# RPI_HAT_Flash_00.net
KiCad netlist of a schematic drawn in Altium Designer
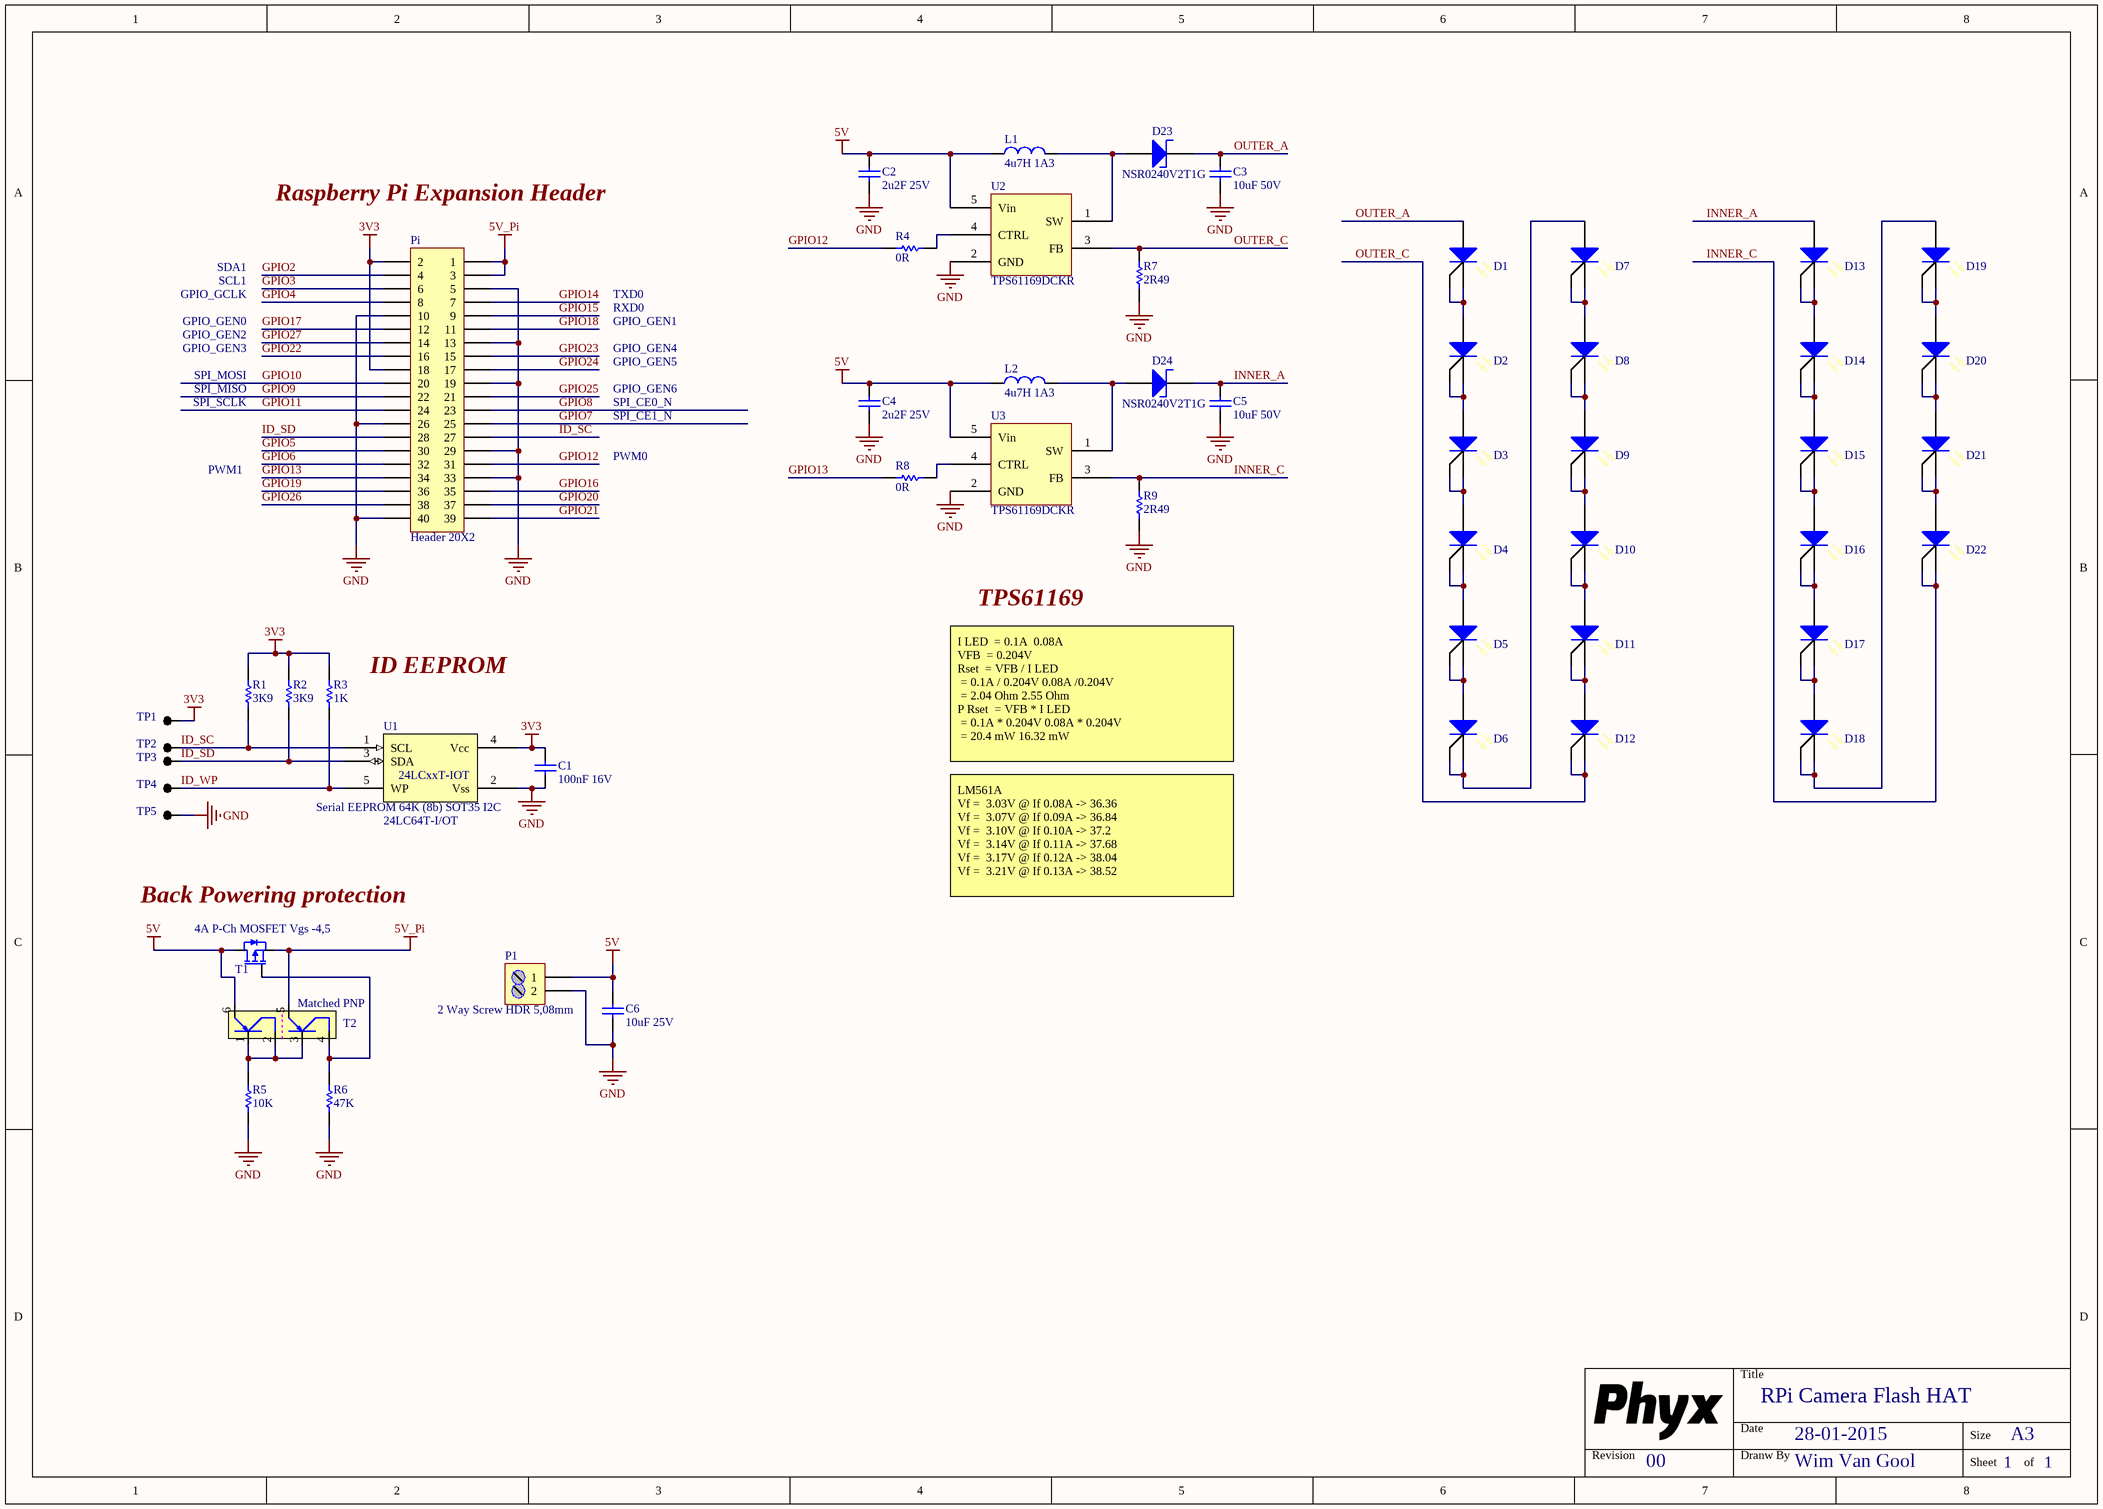
[diagram p0: RPI_HAT_Flash_00.SchDoc]

(export (version "E")
  (design (tool "Eeschema 10.0.6"))
  (components
    (comp (ref "C1")
      (value "100nF 16V")
      (footprint "C0603")
      (description "Capacitor Ceramic")
      (fields (field (name "Comment") "CAP_CERAMIC"))
      (libsource (lib "Phyx_Components") (part "CAP_CERAMIC"))
    )
    (comp (ref "C2")
      (value "2u2F 25V")
      (footprint "C0805")
      (description "Capacitor Ceramic")
      (fields (field (name "Comment") "CAP_CERAMIC"))
      (libsource (lib "Phyx_Components") (part "CAP_CERAMIC"))
    )
    (comp (ref "C3")
      (value "10uF 50V")
      (footprint "C1206")
      (description "Capacitor Ceramic")
      (fields (field (name "Comment") "CAP_CERAMIC"))
      (libsource (lib "Phyx_Components") (part "CAP_CERAMIC"))
    )
    (comp (ref "C4")
      (value "2u2F 25V")
      (footprint "C0805")
      (description "Capacitor Ceramic")
      (fields (field (name "Comment") "CAP_CERAMIC"))
      (libsource (lib "Phyx_Components") (part "CAP_CERAMIC"))
    )
    (comp (ref "C5")
      (value "10uF 50V")
      (footprint "C1206")
      (description "Capacitor Ceramic")
      (fields (field (name "Comment") "CAP_CERAMIC"))
      (libsource (lib "Phyx_Components") (part "CAP_CERAMIC"))
    )
    (comp (ref "C6")
      (value "10uF 25V")
      (footprint "C1206")
      (description "Capacitor Ceramic")
      (fields (field (name "Comment") "CAP_CERAMIC"))
      (libsource (lib "Phyx_Components") (part "CAP_CERAMIC"))
    )
    (comp (ref "D1")
      (value "5630 LM561A Samsung LED")
      (footprint "LED_LM561A")
      (description "=Description")
      (libsource (lib "Phyx_Components") (part "LED_LM561A"))
    )
    (comp (ref "D2")
      (value "5630 LM561A Samsung LED")
      (footprint "LED_LM561A")
      (description "=Description")
      (libsource (lib "Phyx_Components") (part "LED_LM561A"))
    )
    (comp (ref "D3")
      (value "5630 LM561A Samsung LED")
      (footprint "LED_LM561A")
      (description "=Description")
      (libsource (lib "Phyx_Components") (part "LED_LM561A"))
    )
    (comp (ref "D4")
      (value "5630 LM561A Samsung LED")
      (footprint "LED_LM561A")
      (description "=Description")
      (libsource (lib "Phyx_Components") (part "LED_LM561A"))
    )
    (comp (ref "D5")
      (value "5630 LM561A Samsung LED")
      (footprint "LED_LM561A")
      (description "=Description")
      (libsource (lib "Phyx_Components") (part "LED_LM561A"))
    )
    (comp (ref "D6")
      (value "5630 LM561A Samsung LED")
      (footprint "LED_LM561A")
      (description "=Description")
      (libsource (lib "Phyx_Components") (part "LED_LM561A"))
    )
    (comp (ref "D7")
      (value "5630 LM561A Samsung LED")
      (footprint "LED_LM561A")
      (description "=Description")
      (libsource (lib "Phyx_Components") (part "LED_LM561A"))
    )
    (comp (ref "D8")
      (value "5630 LM561A Samsung LED")
      (footprint "LED_LM561A")
      (description "=Description")
      (libsource (lib "Phyx_Components") (part "LED_LM561A"))
    )
    (comp (ref "D9")
      (value "5630 LM561A Samsung LED")
      (footprint "LED_LM561A")
      (description "=Description")
      (libsource (lib "Phyx_Components") (part "LED_LM561A"))
    )
    (comp (ref "D10")
      (value "5630 LM561A Samsung LED")
      (footprint "LED_LM561A")
      (description "=Description")
      (libsource (lib "Phyx_Components") (part "LED_LM561A"))
    )
    (comp (ref "D11")
      (value "5630 LM561A Samsung LED")
      (footprint "LED_LM561A")
      (description "=Description")
      (libsource (lib "Phyx_Components") (part "LED_LM561A"))
    )
    (comp (ref "D12")
      (value "5630 LM561A Samsung LED")
      (footprint "LED_LM561A")
      (description "=Description")
      (libsource (lib "Phyx_Components") (part "LED_LM561A"))
    )
    (comp (ref "D13")
      (value "5630 LM561A Samsung LED")
      (footprint "LED_LM561A")
      (description "=Description")
      (libsource (lib "Phyx_Components") (part "LED_LM561A"))
    )
    (comp (ref "D14")
      (value "5630 LM561A Samsung LED")
      (footprint "LED_LM561A")
      (description "=Description")
      (libsource (lib "Phyx_Components") (part "LED_LM561A"))
    )
    (comp (ref "D15")
      (value "5630 LM561A Samsung LED")
      (footprint "LED_LM561A")
      (description "=Description")
      (libsource (lib "Phyx_Components") (part "LED_LM561A"))
    )
    (comp (ref "D16")
      (value "5630 LM561A Samsung LED")
      (footprint "LED_LM561A")
      (description "=Description")
      (libsource (lib "Phyx_Components") (part "LED_LM561A"))
    )
    (comp (ref "D17")
      (value "5630 LM561A Samsung LED")
      (footprint "LED_LM561A")
      (description "=Description")
      (libsource (lib "Phyx_Components") (part "LED_LM561A"))
    )
    (comp (ref "D18")
      (value "5630 LM561A Samsung LED")
      (footprint "LED_LM561A")
      (description "=Description")
      (libsource (lib "Phyx_Components") (part "LED_LM561A"))
    )
    (comp (ref "D19")
      (value "5630 LM561A Samsung LED")
      (footprint "LED_LM561A")
      (description "=Description")
      (libsource (lib "Phyx_Components") (part "LED_LM561A"))
    )
    (comp (ref "D20")
      (value "5630 LM561A Samsung LED")
      (footprint "LED_LM561A")
      (description "=Description")
      (libsource (lib "Phyx_Components") (part "LED_LM561A"))
    )
    (comp (ref "D21")
      (value "5630 LM561A Samsung LED")
      (footprint "LED_LM561A")
      (description "=Description")
      (libsource (lib "Phyx_Components") (part "LED_LM561A"))
    )
    (comp (ref "D22")
      (value "5630 LM561A Samsung LED")
      (footprint "LED_LM561A")
      (description "=Description")
      (libsource (lib "Phyx_Components") (part "LED_LM561A"))
    )
    (comp (ref "D23")
      (value "NSR0240V2T1G")
      (footprint "ON_SOD-523")
      (description "=Description")
      (fields (field (name "Comment") "NSR0240V2T1G Schottky ULTRAFAST, 200MA, 40V"))
      (libsource (lib "Phyx_Components") (part "Schottky_CA"))
    )
    (comp (ref "D24")
      (value "NSR0240V2T1G")
      (footprint "ON_SOD-523")
      (description "=Description")
      (fields (field (name "Comment") "NSR0240V2T1G Schottky ULTRAFAST, 200MA, 40V"))
      (libsource (lib "Phyx_Components") (part "Schottky_CA"))
    )
    (comp (ref "L1")
      (value "4u7H 1A3")
      (footprint "LPS4018")
      (fields (field (name "Comment") "LPS4018-472MRB"))
      (libsource (lib "Phyx_Components") (part "INDUCTOR"))
    )
    (comp (ref "L2")
      (value "4u7H 1A3")
      (footprint "LPS4018")
      (fields (field (name "Comment") "LPS4018-472MRB"))
      (libsource (lib "Phyx_Components") (part "INDUCTOR"))
    )
    (comp (ref "P1")
      (value "2 Way Screw HDR 5,08mm")
      (footprint "TERM_BLK-0508-2-90")
      (libsource (lib "Phyx_Components") (part "TERM_BLCK_2"))
    )
    (comp (ref "Pi")
      (value "Header 20X2")
      (footprint "RCPT2X20")
      (description "=Description")
      (libsource (lib "Phyx_Components") (part "Header 20X2"))
    )
    (comp (ref "R1")
      (value "3K9")
      (footprint "R0603")
      (fields (field (name "Comment") "RESISTOR"))
      (libsource (lib "Phyx_Components") (part "RESISTOR"))
    )
    (comp (ref "R2")
      (value "3K9")
      (footprint "R0603")
      (fields (field (name "Comment") "RESISTOR"))
      (libsource (lib "Phyx_Components") (part "RESISTOR"))
    )
    (comp (ref "R3")
      (value "1K")
      (footprint "R0603")
      (fields (field (name "Comment") "RESISTOR"))
      (libsource (lib "Phyx_Components") (part "RESISTOR"))
    )
    (comp (ref "R4")
      (value "0R")
      (footprint "R0603")
      (fields (field (name "Comment") "RESISTOR"))
      (libsource (lib "Phyx_Components") (part "RESISTOR"))
    )
    (comp (ref "R5")
      (value "10K")
      (footprint "R0603")
      (fields (field (name "Comment") "RESISTOR"))
      (libsource (lib "Phyx_Components") (part "RESISTOR"))
    )
    (comp (ref "R6")
      (value "47K")
      (footprint "R0603")
      (fields (field (name "Comment") "RESISTOR"))
      (libsource (lib "Phyx_Components") (part "RESISTOR"))
    )
    (comp (ref "R7")
      (value "2R49")
      (footprint "R0603")
      (fields (field (name "Comment") "RESISTOR"))
      (libsource (lib "Phyx_Components") (part "RESISTOR"))
    )
    (comp (ref "R8")
      (value "0R")
      (footprint "R0603")
      (fields (field (name "Comment") "RESISTOR"))
      (libsource (lib "Phyx_Components") (part "RESISTOR"))
    )
    (comp (ref "R9")
      (value "2R49")
      (footprint "R0603")
      (fields (field (name "Comment") "RESISTOR"))
      (libsource (lib "Phyx_Components") (part "RESISTOR"))
    )
    (comp (ref "T1")
      (value "4A P-Ch MOSFET Vgs -4,5")
      (footprint "SOT23-3")
      (description "=Description")
      (libsource (lib "Phyx_Components") (part "P_MOSFET_GSD"))
    )
    (comp (ref "T2")
      (value "Matched PNP")
      (footprint "SOT23-6")
      (libsource (lib "Phyx_Components") (part "DMMT5401"))
    )
    (comp (ref "TP1")
      (value "TEST_PAD")
      (footprint "TP_1.2mm_0.6mm")
      (libsource (lib "Phyx_Components") (part "TEST_PAD"))
    )
    (comp (ref "TP2")
      (value "TEST_PAD")
      (footprint "TP_1.2mm_0.6mm")
      (libsource (lib "Phyx_Components") (part "TEST_PAD"))
    )
    (comp (ref "TP3")
      (value "TEST_PAD")
      (footprint "TP_1.2mm_0.6mm")
      (libsource (lib "Phyx_Components") (part "TEST_PAD"))
    )
    (comp (ref "TP4")
      (value "TEST_PAD")
      (footprint "TP_1.2mm_0.6mm")
      (libsource (lib "Phyx_Components") (part "TEST_PAD"))
    )
    (comp (ref "TP5")
      (value "TEST_PAD")
      (footprint "TP_1.2mm_0.6mm")
      (libsource (lib "Phyx_Components") (part "TEST_PAD"))
    )
    (comp (ref "U1")
      (value "Serial EEPROM 64K (8b) SOT35 I2C")
      (footprint "SOT23-5")
      (description "=Description")
      (fields (field (name "ALTIUM_VALUE") "24LC64T-I/OT"))
      (libsource (lib "Phyx_Components") (part "24LCxxT-IOT"))
    )
    (comp (ref "U2")
      (value "TPS61169DCKR")
      (footprint "TI-DCK-R-PDSO-G5")
      (description "=Description")
      (fields (field (name "Comment") "TPS61169 38-V Boost WLED Driver with PWM"))
      (libsource (lib "Phyx_Components") (part "TPS61169"))
    )
    (comp (ref "U3")
      (value "TPS61169DCKR")
      (footprint "TI-DCK-R-PDSO-G5")
      (description "=Description")
      (fields (field (name "Comment") "TPS61169 38-V Boost WLED Driver with PWM"))
      (libsource (lib "Phyx_Components") (part "TPS61169"))
    )
  )
  (nets
    (net (code "1") (name "/GPIO2") (class "Default")
      (node (ref "Pi") (pin "4") (pinfunction "4_4") (pintype "passive"))
    )
    (net (code "2") (name "/GPIO3") (class "Default")
      (node (ref "Pi") (pin "6") (pinfunction "6_6") (pintype "passive"))
    )
    (net (code "3") (name "/GPIO4") (class "Default")
      (node (ref "Pi") (pin "8") (pinfunction "8_8") (pintype "passive"))
    )
    (net (code "4") (name "/GPIO5") (class "Default")
      (node (ref "Pi") (pin "30") (pinfunction "30_30") (pintype "passive"))
    )
    (net (code "5") (name "/GPIO6") (class "Default")
      (node (ref "Pi") (pin "32") (pinfunction "32_32") (pintype "passive"))
    )
    (net (code "6") (name "/GPIO7") (class "Default")
      (node (ref "Pi") (pin "25") (pinfunction "25_25") (pintype "passive"))
    )
    (net (code "7") (name "/GPIO8") (class "Default")
      (node (ref "Pi") (pin "23") (pinfunction "23_23") (pintype "passive"))
    )
    (net (code "8") (name "/GPIO9") (class "Default")
      (node (ref "Pi") (pin "22") (pinfunction "22_22") (pintype "passive"))
    )
    (net (code "9") (name "/GPIO10") (class "Default")
      (node (ref "Pi") (pin "20") (pinfunction "20_20") (pintype "passive"))
    )
    (net (code "10") (name "/GPIO11") (class "Default")
      (node (ref "Pi") (pin "24") (pinfunction "24_24") (pintype "passive"))
    )
    (net (code "11") (name "/GPIO12") (class "Default")
      (node (ref "Pi") (pin "31") (pinfunction "31_31") (pintype "passive"))
      (node (ref "R4") (pin "2") (pinfunction "2_2") (pintype "passive"))
    )
    (net (code "12") (name "/GPIO13") (class "Default")
      (node (ref "Pi") (pin "34") (pinfunction "34_34") (pintype "passive"))
      (node (ref "R8") (pin "2") (pinfunction "2_2") (pintype "passive"))
    )
    (net (code "13") (name "/GPIO14") (class "Default")
      (node (ref "Pi") (pin "7") (pinfunction "7_7") (pintype "passive"))
    )
    (net (code "14") (name "/GPIO15") (class "Default")
      (node (ref "Pi") (pin "9") (pinfunction "9_9") (pintype "passive"))
    )
    (net (code "15") (name "/GPIO16") (class "Default")
      (node (ref "Pi") (pin "35") (pinfunction "35_35") (pintype "passive"))
    )
    (net (code "16") (name "/GPIO17") (class "Default")
      (node (ref "Pi") (pin "12") (pinfunction "12_12") (pintype "passive"))
    )
    (net (code "17") (name "/GPIO18") (class "Default")
      (node (ref "Pi") (pin "11") (pinfunction "11_11") (pintype "passive"))
    )
    (net (code "18") (name "/GPIO19") (class "Default")
      (node (ref "Pi") (pin "36") (pinfunction "36_36") (pintype "passive"))
    )
    (net (code "19") (name "/GPIO20") (class "Default")
      (node (ref "Pi") (pin "37") (pinfunction "37_37") (pintype "passive"))
    )
    (net (code "20") (name "/GPIO21") (class "Default")
      (node (ref "Pi") (pin "39") (pinfunction "39_39") (pintype "passive"))
    )
    (net (code "21") (name "/GPIO22") (class "Default")
      (node (ref "Pi") (pin "16") (pinfunction "16_16") (pintype "passive"))
    )
    (net (code "22") (name "/GPIO23") (class "Default")
      (node (ref "Pi") (pin "15") (pinfunction "15_15") (pintype "passive"))
    )
    (net (code "23") (name "/GPIO24") (class "Default")
      (node (ref "Pi") (pin "17") (pinfunction "17_17") (pintype "passive"))
    )
    (net (code "24") (name "/GPIO25") (class "Default")
      (node (ref "Pi") (pin "21") (pinfunction "21_21") (pintype "passive"))
    )
    (net (code "25") (name "/GPIO26") (class "Default")
      (node (ref "Pi") (pin "38") (pinfunction "38_38") (pintype "passive"))
    )
    (net (code "26") (name "/GPIO27") (class "Default")
      (node (ref "Pi") (pin "14") (pinfunction "14_14") (pintype "passive"))
    )
    (net (code "27") (name "/ID_SC") (class "Default")
      (node (ref "Pi") (pin "27") (pinfunction "27_27") (pintype "passive"))
      (node (ref "R1") (pin "2") (pinfunction "2_2") (pintype "passive"))
      (node (ref "TP2") (pin "1") (pinfunction "1_1") (pintype "passive"))
      (node (ref "U1") (pin "1") (pinfunction "SCL_1") (pintype "input"))
    )
    (net (code "28") (name "/ID_SD") (class "Default")
      (node (ref "Pi") (pin "28") (pinfunction "28_28") (pintype "passive"))
      (node (ref "R2") (pin "2") (pinfunction "2_2") (pintype "passive"))
      (node (ref "TP3") (pin "1") (pinfunction "1_1") (pintype "passive"))
      (node (ref "U1") (pin "3") (pinfunction "SDA_3") (pintype "bidirectional"))
    )
    (net (code "29") (name "/ID_WP") (class "Default")
      (node (ref "R3") (pin "2") (pinfunction "2_2") (pintype "passive"))
      (node (ref "TP4") (pin "1") (pinfunction "1_1") (pintype "passive"))
      (node (ref "U1") (pin "5") (pinfunction "WP_5") (pintype "passive"))
    )
    (net (code "30") (name "/INNER_A") (class "Default")
      (node (ref "C5") (pin "1") (pinfunction "1_1") (pintype "passive"))
      (node (ref "D13") (pin "1") (pinfunction "A_1") (pintype "passive"))
      (node (ref "D24") (pin "1") (pinfunction "C_1") (pintype "passive"))
    )
    (net (code "31") (name "/INNER_C") (class "Default")
      (node (ref "D22") (pin "2") (pinfunction "K_2") (pintype "passive"))
      (node (ref "D22") (pin "3") (pinfunction "K_3") (pintype "passive"))
      (node (ref "R9") (pin "1") (pinfunction "1_1") (pintype "passive"))
      (node (ref "U3") (pin "3") (pinfunction "FB_3") (pintype "passive"))
    )
    (net (code "32") (name "/OUTER_A") (class "Default")
      (node (ref "C3") (pin "1") (pinfunction "1_1") (pintype "passive"))
      (node (ref "D1") (pin "1") (pinfunction "A_1") (pintype "passive"))
      (node (ref "D23") (pin "1") (pinfunction "C_1") (pintype "passive"))
    )
    (net (code "33") (name "/OUTER_C") (class "Default")
      (node (ref "D12") (pin "2") (pinfunction "K_2") (pintype "passive"))
      (node (ref "D12") (pin "3") (pinfunction "K_3") (pintype "passive"))
      (node (ref "R7") (pin "1") (pinfunction "1_1") (pintype "passive"))
      (node (ref "U2") (pin "3") (pinfunction "FB_3") (pintype "passive"))
    )
    (net (code "34") (name "3V3") (class "Default")
      (node (ref "C1") (pin "1") (pinfunction "1_1") (pintype "passive"))
      (node (ref "Pi") (pin "18") (pinfunction "18_18") (pintype "passive"))
      (node (ref "Pi") (pin "2") (pinfunction "2_2") (pintype "passive"))
      (node (ref "R1") (pin "1") (pinfunction "1_1") (pintype "passive"))
      (node (ref "R2") (pin "1") (pinfunction "1_1") (pintype "passive"))
      (node (ref "R3") (pin "1") (pinfunction "1_1") (pintype "passive"))
      (node (ref "TP1") (pin "1") (pinfunction "1_1") (pintype "passive"))
      (node (ref "U1") (pin "4") (pinfunction "Vcc_4") (pintype "passive"))
    )
    (net (code "35") (name "5V") (class "Default")
      (node (ref "C2") (pin "1") (pinfunction "1_1") (pintype "passive"))
      (node (ref "C4") (pin "1") (pinfunction "1_1") (pintype "passive"))
      (node (ref "C6") (pin "1") (pinfunction "1_1") (pintype "passive"))
      (node (ref "L1") (pin "1") (pinfunction "1_1") (pintype "passive"))
      (node (ref "L2") (pin "1") (pinfunction "1_1") (pintype "passive"))
      (node (ref "P1") (pin "1") (pinfunction "1_1") (pintype "passive"))
      (node (ref "T1") (pin "3") (pinfunction "D_3") (pintype "passive"))
      (node (ref "T2") (pin "6") (pinfunction "E_6") (pintype "passive"))
      (node (ref "U2") (pin "5") (pinfunction "Vin_5") (pintype "passive"))
      (node (ref "U3") (pin "5") (pinfunction "Vin_5") (pintype "passive"))
    )
    (net (code "36") (name "5V_Pi") (class "Default")
      (node (ref "Pi") (pin "1") (pinfunction "1_1") (pintype "passive"))
      (node (ref "Pi") (pin "3") (pinfunction "3_3") (pintype "passive"))
      (node (ref "T1") (pin "2") (pinfunction "S_2") (pintype "passive"))
      (node (ref "T2") (pin "5") (pinfunction "E_5") (pintype "passive"))
    )
    (net (code "37") (name "GND") (class "Default")
      (node (ref "C1") (pin "2") (pinfunction "2_2") (pintype "passive"))
      (node (ref "C2") (pin "2") (pinfunction "2_2") (pintype "passive"))
      (node (ref "C3") (pin "2") (pinfunction "2_2") (pintype "passive"))
      (node (ref "C4") (pin "2") (pinfunction "2_2") (pintype "passive"))
      (node (ref "C5") (pin "2") (pinfunction "2_2") (pintype "passive"))
      (node (ref "C6") (pin "2") (pinfunction "2_2") (pintype "passive"))
      (node (ref "P1") (pin "2") (pinfunction "2_2") (pintype "passive"))
      (node (ref "Pi") (pin "10") (pinfunction "10_10") (pintype "passive"))
      (node (ref "Pi") (pin "13") (pinfunction "13_13") (pintype "passive"))
      (node (ref "Pi") (pin "19") (pinfunction "19_19") (pintype "passive"))
      (node (ref "Pi") (pin "26") (pinfunction "26_26") (pintype "passive"))
      (node (ref "Pi") (pin "29") (pinfunction "29_29") (pintype "passive"))
      (node (ref "Pi") (pin "33") (pinfunction "33_33") (pintype "passive"))
      (node (ref "Pi") (pin "40") (pinfunction "40_40") (pintype "passive"))
      (node (ref "Pi") (pin "5") (pinfunction "5_5") (pintype "passive"))
      (node (ref "R5") (pin "2") (pinfunction "2_2") (pintype "passive"))
      (node (ref "R6") (pin "2") (pinfunction "2_2") (pintype "passive"))
      (node (ref "R7") (pin "2") (pinfunction "2_2") (pintype "passive"))
      (node (ref "R9") (pin "2") (pinfunction "2_2") (pintype "passive"))
      (node (ref "TP5") (pin "1") (pinfunction "1_1") (pintype "passive"))
      (node (ref "U1") (pin "2") (pinfunction "Vss_2") (pintype "passive"))
      (node (ref "U2") (pin "2") (pinfunction "GND_2") (pintype "passive"))
      (node (ref "U3") (pin "2") (pinfunction "GND_2") (pintype "passive"))
    )
    (net (code "38") (name "Net-(D2-A)") (class "Default")
      (node (ref "D1") (pin "2") (pinfunction "K_2") (pintype "passive"))
      (node (ref "D1") (pin "3") (pinfunction "K_3") (pintype "passive"))
      (node (ref "D2") (pin "1") (pinfunction "A_1") (pintype "passive"))
    )
    (net (code "39") (name "Net-(D3-A)") (class "Default")
      (node (ref "D2") (pin "2") (pinfunction "K_2") (pintype "passive"))
      (node (ref "D2") (pin "3") (pinfunction "K_3") (pintype "passive"))
      (node (ref "D3") (pin "1") (pinfunction "A_1") (pintype "passive"))
    )
    (net (code "40") (name "Net-(D4-A)") (class "Default")
      (node (ref "D3") (pin "2") (pinfunction "K_2") (pintype "passive"))
      (node (ref "D3") (pin "3") (pinfunction "K_3") (pintype "passive"))
      (node (ref "D4") (pin "1") (pinfunction "A_1") (pintype "passive"))
    )
    (net (code "41") (name "Net-(D5-A)") (class "Default")
      (node (ref "D4") (pin "2") (pinfunction "K_2") (pintype "passive"))
      (node (ref "D4") (pin "3") (pinfunction "K_3") (pintype "passive"))
      (node (ref "D5") (pin "1") (pinfunction "A_1") (pintype "passive"))
    )
    (net (code "42") (name "Net-(D6-A)") (class "Default")
      (node (ref "D5") (pin "2") (pinfunction "K_2") (pintype "passive"))
      (node (ref "D5") (pin "3") (pinfunction "K_3") (pintype "passive"))
      (node (ref "D6") (pin "1") (pinfunction "A_1") (pintype "passive"))
    )
    (net (code "43") (name "Net-(D7-A)") (class "Default")
      (node (ref "D6") (pin "2") (pinfunction "K_2") (pintype "passive"))
      (node (ref "D6") (pin "3") (pinfunction "K_3") (pintype "passive"))
      (node (ref "D7") (pin "1") (pinfunction "A_1") (pintype "passive"))
    )
    (net (code "44") (name "Net-(D8-A)") (class "Default")
      (node (ref "D7") (pin "2") (pinfunction "K_2") (pintype "passive"))
      (node (ref "D7") (pin "3") (pinfunction "K_3") (pintype "passive"))
      (node (ref "D8") (pin "1") (pinfunction "A_1") (pintype "passive"))
    )
    (net (code "45") (name "Net-(D9-A)") (class "Default")
      (node (ref "D8") (pin "2") (pinfunction "K_2") (pintype "passive"))
      (node (ref "D8") (pin "3") (pinfunction "K_3") (pintype "passive"))
      (node (ref "D9") (pin "1") (pinfunction "A_1") (pintype "passive"))
    )
    (net (code "46") (name "Net-(D10-A)") (class "Default")
      (node (ref "D10") (pin "1") (pinfunction "A_1") (pintype "passive"))
      (node (ref "D9") (pin "2") (pinfunction "K_2") (pintype "passive"))
      (node (ref "D9") (pin "3") (pinfunction "K_3") (pintype "passive"))
    )
    (net (code "47") (name "Net-(D11-A)") (class "Default")
      (node (ref "D10") (pin "2") (pinfunction "K_2") (pintype "passive"))
      (node (ref "D10") (pin "3") (pinfunction "K_3") (pintype "passive"))
      (node (ref "D11") (pin "1") (pinfunction "A_1") (pintype "passive"))
    )
    (net (code "48") (name "Net-(D12-A)") (class "Default")
      (node (ref "D11") (pin "2") (pinfunction "K_2") (pintype "passive"))
      (node (ref "D11") (pin "3") (pinfunction "K_3") (pintype "passive"))
      (node (ref "D12") (pin "1") (pinfunction "A_1") (pintype "passive"))
    )
    (net (code "49") (name "Net-(D14-A)") (class "Default")
      (node (ref "D13") (pin "2") (pinfunction "K_2") (pintype "passive"))
      (node (ref "D13") (pin "3") (pinfunction "K_3") (pintype "passive"))
      (node (ref "D14") (pin "1") (pinfunction "A_1") (pintype "passive"))
    )
    (net (code "50") (name "Net-(D15-A)") (class "Default")
      (node (ref "D14") (pin "2") (pinfunction "K_2") (pintype "passive"))
      (node (ref "D14") (pin "3") (pinfunction "K_3") (pintype "passive"))
      (node (ref "D15") (pin "1") (pinfunction "A_1") (pintype "passive"))
    )
    (net (code "51") (name "Net-(D16-A)") (class "Default")
      (node (ref "D15") (pin "2") (pinfunction "K_2") (pintype "passive"))
      (node (ref "D15") (pin "3") (pinfunction "K_3") (pintype "passive"))
      (node (ref "D16") (pin "1") (pinfunction "A_1") (pintype "passive"))
    )
    (net (code "52") (name "Net-(D17-A)") (class "Default")
      (node (ref "D16") (pin "2") (pinfunction "K_2") (pintype "passive"))
      (node (ref "D16") (pin "3") (pinfunction "K_3") (pintype "passive"))
      (node (ref "D17") (pin "1") (pinfunction "A_1") (pintype "passive"))
    )
    (net (code "53") (name "Net-(D18-A)") (class "Default")
      (node (ref "D17") (pin "2") (pinfunction "K_2") (pintype "passive"))
      (node (ref "D17") (pin "3") (pinfunction "K_3") (pintype "passive"))
      (node (ref "D18") (pin "1") (pinfunction "A_1") (pintype "passive"))
    )
    (net (code "54") (name "Net-(D19-A)") (class "Default")
      (node (ref "D18") (pin "2") (pinfunction "K_2") (pintype "passive"))
      (node (ref "D18") (pin "3") (pinfunction "K_3") (pintype "passive"))
      (node (ref "D19") (pin "1") (pinfunction "A_1") (pintype "passive"))
    )
    (net (code "55") (name "Net-(D20-A)") (class "Default")
      (node (ref "D19") (pin "2") (pinfunction "K_2") (pintype "passive"))
      (node (ref "D19") (pin "3") (pinfunction "K_3") (pintype "passive"))
      (node (ref "D20") (pin "1") (pinfunction "A_1") (pintype "passive"))
    )
    (net (code "56") (name "Net-(D21-A)") (class "Default")
      (node (ref "D20") (pin "2") (pinfunction "K_2") (pintype "passive"))
      (node (ref "D20") (pin "3") (pinfunction "K_3") (pintype "passive"))
      (node (ref "D21") (pin "1") (pinfunction "A_1") (pintype "passive"))
    )
    (net (code "57") (name "Net-(D22-A)") (class "Default")
      (node (ref "D21") (pin "2") (pinfunction "K_2") (pintype "passive"))
      (node (ref "D21") (pin "3") (pinfunction "K_3") (pintype "passive"))
      (node (ref "D22") (pin "1") (pinfunction "A_1") (pintype "passive"))
    )
    (net (code "58") (name "Net-(D23-A)") (class "Default")
      (node (ref "D23") (pin "2") (pinfunction "A_2") (pintype "passive"))
      (node (ref "L1") (pin "2") (pinfunction "2_2") (pintype "passive"))
      (node (ref "U2") (pin "1") (pinfunction "SW_1") (pintype "passive"))
    )
    (net (code "59") (name "Net-(D24-A)") (class "Default")
      (node (ref "D24") (pin "2") (pinfunction "A_2") (pintype "passive"))
      (node (ref "L2") (pin "2") (pinfunction "2_2") (pintype "passive"))
      (node (ref "U3") (pin "1") (pinfunction "SW_1") (pintype "passive"))
    )
    (net (code "60") (name "Net-(R5-Pad1)") (class "Default")
      (node (ref "R5") (pin "1") (pinfunction "1_1") (pintype "passive"))
      (node (ref "T2") (pin "1") (pinfunction "B_1") (pintype "passive"))
      (node (ref "T2") (pin "2") (pinfunction "C_2") (pintype "passive"))
      (node (ref "T2") (pin "3") (pinfunction "B_3") (pintype "passive"))
    )
    (net (code "61") (name "Net-(T1-G)") (class "Default")
      (node (ref "R6") (pin "1") (pinfunction "1_1") (pintype "passive"))
      (node (ref "T1") (pin "1") (pinfunction "G_1") (pintype "passive"))
      (node (ref "T2") (pin "4") (pinfunction "C_4") (pintype "passive"))
    )
    (net (code "62") (name "Net-(U2-CTRL)") (class "Default")
      (node (ref "R4") (pin "1") (pinfunction "1_1") (pintype "passive"))
      (node (ref "U2") (pin "4") (pinfunction "CTRL_4") (pintype "passive"))
    )
    (net (code "63") (name "Net-(U3-CTRL)") (class "Default")
      (node (ref "R8") (pin "1") (pinfunction "1_1") (pintype "passive"))
      (node (ref "U3") (pin "4") (pinfunction "CTRL_4") (pintype "passive"))
    )
  )
)
